# SignalGen_SingleChannel.net
KiCad netlist of a schematic drawn in Altium Designer
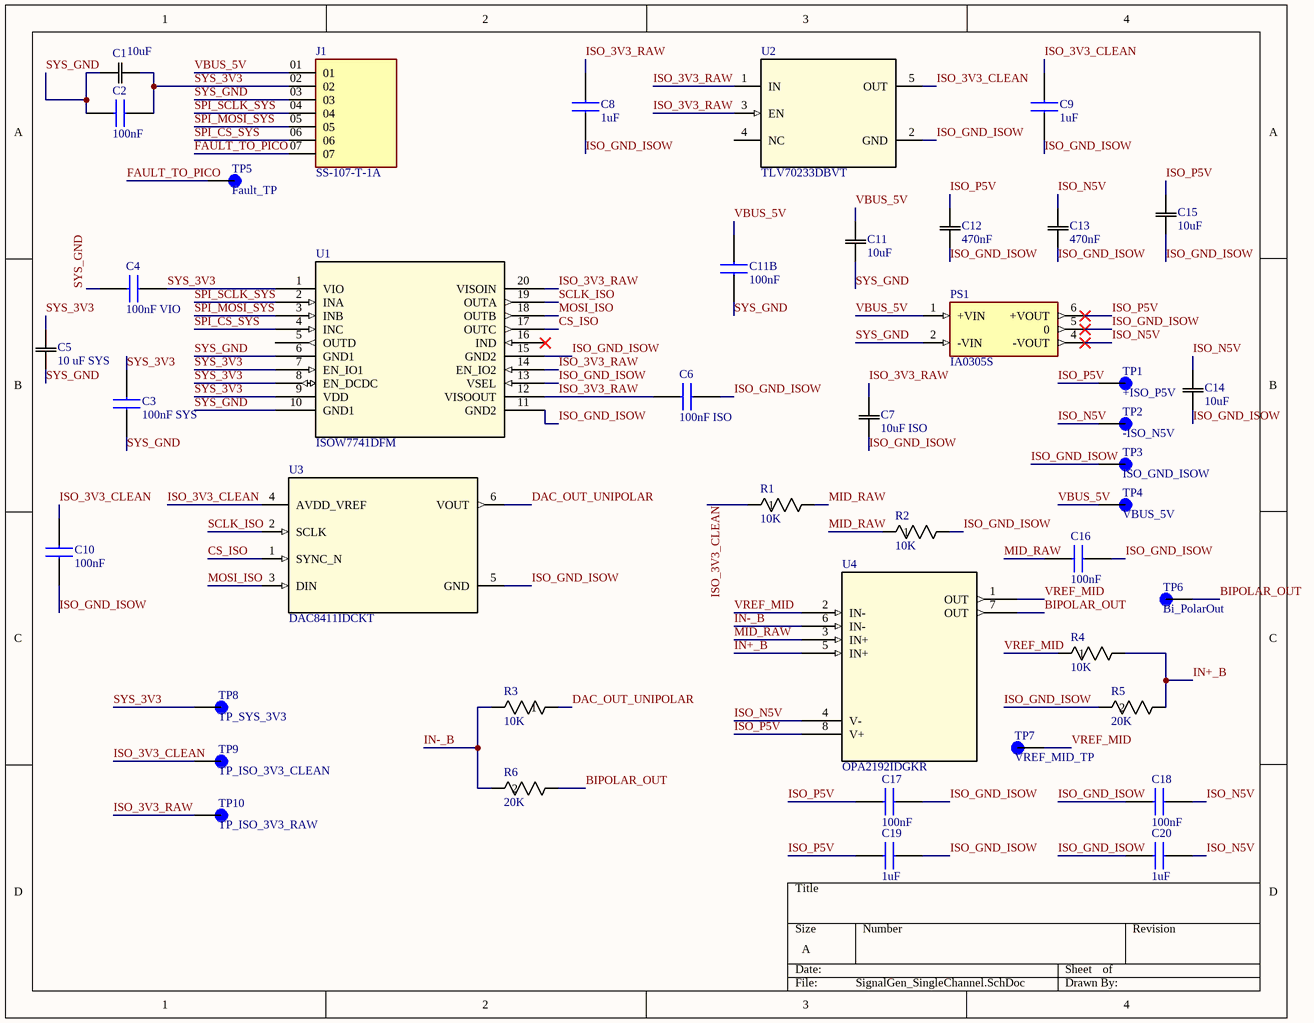
[diagram p0: SignalGen_SingleChannel.SchDoc]

(export (version "E")
  (design (tool "Eeschema 10.0.6"))
  (components
    (comp (ref "C1")
      (value "10uF")
      (footprint "G-21_MUR")
      (description "Description")
      (fields
        (field (name "MANUFACTURER_PART_NUMBER") "GRM21BR61E106KA73L")
        (field (name "COPYRIGHT") "Copyright (C) 2025 Ultra Librarian. All rights reserved.")
      )
      (libsource (lib "GRM21BR61E106KA73L") (part "GRM21BR61E106KA73L"))
    )
    (comp (ref "C2")
      (value "100nF")
      (footprint "CAPC1608X90N")
      (description "Cap Ceramic 0.1uF 25V X7R 10% Pad SMD 0603 125C T/R")
      (fields
        (field (name "MOUSER PART NUMBER") "603-CC603KRX7R8BB104")
        (field (name "MANUFACTURER_PART_NUMBER") "CC0603KRX7R8BB104")
      )
      (libsource (lib "CC0603KRX7R8BB104") (part "CC0603KRX7R8BB104"))
    )
    (comp (ref "C3")
      (value "100nF SYS")
      (footprint "CAPC1608X90N")
      (description "Cap Ceramic 0.1uF 25V X7R 10% Pad SMD 0603 125C T/R")
      (fields
        (field (name "MOUSER PART NUMBER") "603-CC603KRX7R8BB104")
        (field (name "MANUFACTURER_PART_NUMBER") "CC0603KRX7R8BB104")
      )
      (libsource (lib "CC0603KRX7R8BB104") (part "CC0603KRX7R8BB104"))
    )
    (comp (ref "C4")
      (value "100nF VIO")
      (footprint "CAPC1608X90N")
      (description "Cap Ceramic 0.1uF 25V X7R 10% Pad SMD 0603 125C T/R")
      (fields
        (field (name "MOUSER PART NUMBER") "603-CC603KRX7R8BB104")
        (field (name "MANUFACTURER_PART_NUMBER") "CC0603KRX7R8BB104")
      )
      (libsource (lib "CC0603KRX7R8BB104") (part "CC0603KRX7R8BB104"))
    )
    (comp (ref "C5")
      (value "10 uF SYS")
      (footprint "G-21_MUR")
      (description "Description")
      (fields
        (field (name "MANUFACTURER_PART_NUMBER") "GRM21BR61E106KA73L")
        (field (name "COPYRIGHT") "Copyright (C) 2025 Ultra Librarian. All rights reserved.")
      )
      (libsource (lib "GRM21BR61E106KA73L") (part "GRM21BR61E106KA73L"))
    )
    (comp (ref "C6")
      (value "100nF ISO")
      (footprint "CAPC1608X90N")
      (description "Cap Ceramic 0.1uF 25V X7R 10% Pad SMD 0603 125C T/R")
      (fields
        (field (name "MOUSER PART NUMBER") "603-CC603KRX7R8BB104")
        (field (name "MANUFACTURER_PART_NUMBER") "CC0603KRX7R8BB104")
      )
      (libsource (lib "CC0603KRX7R8BB104") (part "CC0603KRX7R8BB104"))
    )
    (comp (ref "C7")
      (value "10uF ISO")
      (footprint "G-21_MUR")
      (description "Description")
      (fields
        (field (name "MANUFACTURER_PART_NUMBER") "GRM21BR61E106KA73L")
        (field (name "COPYRIGHT") "Copyright (C) 2025 Ultra Librarian. All rights reserved.")
      )
      (libsource (lib "GRM21BR61E106KA73L") (part "GRM21BR61E106KA73L"))
    )
    (comp (ref "C8")
      (value "1uF")
      (footprint "INDC1608X90N")
      (description "Taiyo Yuden CAP, MLCC, 0603, 16V, X7R, 1 uF 10 %, T&R")
      (fields (field (name "MANUFACTURER_PART_NUMBER") "MBASE168SB7105KTNA18"))
      (libsource (lib "MBASE168SB7105KTNA18") (part "MBASE168SB7105KTNA18"))
    )
    (comp (ref "C9")
      (value "1uF")
      (footprint "INDC1608X90N")
      (description "Taiyo Yuden CAP, MLCC, 0603, 16V, X7R, 1 uF 10 %, T&R")
      (fields (field (name "MANUFACTURER_PART_NUMBER") "MBASE168SB7105KTNA18"))
      (libsource (lib "MBASE168SB7105KTNA18") (part "MBASE168SB7105KTNA18"))
    )
    (comp (ref "C10")
      (value "100nF")
      (footprint "CAPC1608X90N")
      (description "Cap Ceramic 0.1uF 25V X7R 10% Pad SMD 0603 125C T/R")
      (fields
        (field (name "MOUSER PART NUMBER") "603-CC603KRX7R8BB104")
        (field (name "MANUFACTURER_PART_NUMBER") "CC0603KRX7R8BB104")
      )
      (libsource (lib "CC0603KRX7R8BB104") (part "CC0603KRX7R8BB104"))
    )
    (comp (ref "C11")
      (value "10uF")
      (footprint "G-21_MUR")
      (description "Description")
      (fields
        (field (name "MANUFACTURER_PART_NUMBER") "GRM21BR61E106KA73L")
        (field (name "COPYRIGHT") "Copyright (C) 2025 Ultra Librarian. All rights reserved.")
      )
      (libsource (lib "GRM21BR61E106KA73L") (part "GRM21BR61E106KA73L"))
    )
    (comp (ref "C11B")
      (value "100nF")
      (footprint "CAPC1608X90N")
      (description "Cap Ceramic 0.1uF 25V X7R 10% Pad SMD 0603 125C T/R")
      (fields
        (field (name "MOUSER PART NUMBER") "603-CC603KRX7R8BB104")
        (field (name "MANUFACTURER_PART_NUMBER") "CC0603KRX7R8BB104")
      )
      (libsource (lib "CC0603KRX7R8BB104") (part "CC0603KRX7R8BB104"))
    )
    (comp (ref "C12")
      (value "470nF")
      (footprint "CAP_1608_TDK")
      (description "CAPACITOR; SMT (0603); CERAMIC CHIP; 0.47UF; 50V; TOL=10%; TG=-55 DEGC TO +125 DEGC; TC=X7R; AUTO")
      (fields
        (field (name "MANUFACTURER_PART_NUMBER") "C1608X7R1H474K080AC")
        (field (name "COPYRIGHT") "Copyright (C) 2026 Ultra Librarian. All rights reserved.")
      )
      (libsource (lib "C1608X7R1H474K080AC") (part "C1608X7R1H474K080AC"))
    )
    (comp (ref "C13")
      (value "470nF")
      (footprint "CAP_1608_TDK")
      (description "CAPACITOR; SMT (0603); CERAMIC CHIP; 0.47UF; 50V; TOL=10%; TG=-55 DEGC TO +125 DEGC; TC=X7R; AUTO")
      (fields
        (field (name "MANUFACTURER_PART_NUMBER") "C1608X7R1H474K080AC")
        (field (name "COPYRIGHT") "Copyright (C) 2026 Ultra Librarian. All rights reserved.")
      )
      (libsource (lib "C1608X7R1H474K080AC") (part "C1608X7R1H474K080AC"))
    )
    (comp (ref "C14")
      (value "10uF")
      (footprint "G-21_MUR")
      (description "Description")
      (fields
        (field (name "MANUFACTURER_PART_NUMBER") "GRM21BR61E106KA73L")
        (field (name "COPYRIGHT") "Copyright (C) 2025 Ultra Librarian. All rights reserved.")
      )
      (libsource (lib "GRM21BR61E106KA73L") (part "GRM21BR61E106KA73L"))
    )
    (comp (ref "C15")
      (value "10uF")
      (footprint "G-21_MUR")
      (description "Description")
      (fields
        (field (name "MANUFACTURER_PART_NUMBER") "GRM21BR61E106KA73L")
        (field (name "COPYRIGHT") "Copyright (C) 2025 Ultra Librarian. All rights reserved.")
      )
      (libsource (lib "GRM21BR61E106KA73L") (part "GRM21BR61E106KA73L"))
    )
    (comp (ref "C16")
      (value "100nF")
      (footprint "CAPC1608X90N")
      (description "Cap Ceramic 0.1uF 25V X7R 10% Pad SMD 0603 125C T/R")
      (fields
        (field (name "MOUSER PART NUMBER") "603-CC603KRX7R8BB104")
        (field (name "MANUFACTURER_PART_NUMBER") "CC0603KRX7R8BB104")
      )
      (libsource (lib "CC0603KRX7R8BB104") (part "CC0603KRX7R8BB104"))
    )
    (comp (ref "C17")
      (value "100nF")
      (footprint "CAPC1608X90N")
      (description "Cap Ceramic 0.1uF 25V X7R 10% Pad SMD 0603 125C T/R")
      (fields
        (field (name "MOUSER PART NUMBER") "603-CC603KRX7R8BB104")
        (field (name "MANUFACTURER_PART_NUMBER") "CC0603KRX7R8BB104")
      )
      (libsource (lib "CC0603KRX7R8BB104") (part "CC0603KRX7R8BB104"))
    )
    (comp (ref "C18")
      (value "100nF")
      (footprint "CAPC1608X90N")
      (description "Cap Ceramic 0.1uF 25V X7R 10% Pad SMD 0603 125C T/R")
      (fields
        (field (name "MOUSER PART NUMBER") "603-CC603KRX7R8BB104")
        (field (name "MANUFACTURER_PART_NUMBER") "CC0603KRX7R8BB104")
      )
      (libsource (lib "CC0603KRX7R8BB104") (part "CC0603KRX7R8BB104"))
    )
    (comp (ref "C19")
      (value "1uF")
      (footprint "INDC1608X90N")
      (description "Taiyo Yuden CAP, MLCC, 0603, 16V, X7R, 1 uF 10 %, T&R")
      (fields (field (name "MANUFACTURER_PART_NUMBER") "MBASE168SB7105KTNA18"))
      (libsource (lib "MBASE168SB7105KTNA18") (part "MBASE168SB7105KTNA18"))
    )
    (comp (ref "C20")
      (value "1uF")
      (footprint "INDC1608X90N")
      (description "Taiyo Yuden CAP, MLCC, 0603, 16V, X7R, 1 uF 10 %, T&R")
      (fields (field (name "MANUFACTURER_PART_NUMBER") "MBASE168SB7105KTNA18"))
      (libsource (lib "MBASE168SB7105KTNA18") (part "MBASE168SB7105KTNA18"))
    )
    (comp (ref "J1")
      (value "SS-107-T-1A")
      (footprint "SAMTEC_SS-107-T-1A")
      (libsource (lib "SS-107-T-1A") (part "SS-107-T-1A"))
    )
    (comp (ref "PS1")
      (value "IA0305S")
      (footprint "XP_IA0305S")
      (description "DC DC CONVERTER +/-5V 1W")
      (libsource (lib "IA0305S") (part "IA0305S"))
    )
    (comp (ref "R1")
      (value "10K")
      (footprint "RC0603N_YAG")
      (description "RES SMD 10kO 1% 1/10W 0603")
      (fields
        (field (name "MANUFACTURER_PART_NUMBER") "RC0603FR-0710KL")
        (field (name "COPYRIGHT") "Copyright (C) 2025 Ultra Librarian. All rights reserved.")
      )
      (libsource (lib "RC0603FR-0710KL") (part "RC0603FR-0710KL"))
    )
    (comp (ref "R2")
      (value "10K")
      (footprint "RC0603N_YAG")
      (description "RES SMD 10kO 1% 1/10W 0603")
      (fields
        (field (name "MANUFACTURER_PART_NUMBER") "RC0603FR-0710KL")
        (field (name "COPYRIGHT") "Copyright (C) 2025 Ultra Librarian. All rights reserved.")
      )
      (libsource (lib "RC0603FR-0710KL") (part "RC0603FR-0710KL"))
    )
    (comp (ref "R3")
      (value "10K")
      (footprint "RC0603N_YAG")
      (description "RES SMD 10kO 1% 1/10W 0603")
      (fields
        (field (name "MANUFACTURER_PART_NUMBER") "RC0603FR-0710KL")
        (field (name "COPYRIGHT") "Copyright (C) 2025 Ultra Librarian. All rights reserved.")
      )
      (libsource (lib "RC0603FR-0710KL") (part "RC0603FR-0710KL"))
    )
    (comp (ref "R4")
      (value "10K")
      (footprint "RC0603N_YAG")
      (description "RES SMD 10kO 1% 1/10W 0603")
      (fields
        (field (name "MANUFACTURER_PART_NUMBER") "RC0603FR-0710KL")
        (field (name "COPYRIGHT") "Copyright (C) 2025 Ultra Librarian. All rights reserved.")
      )
      (libsource (lib "RC0603FR-0710KL") (part "RC0603FR-0710KL"))
    )
    (comp (ref "R5")
      (value "20K")
      (footprint "RC0603N_YAG")
      (description "Description")
      (fields
        (field (name "MANUFACTURER_PART_NUMBER") "RC0603FR-0720KL")
        (field (name "COPYRIGHT") "Copyright (C) 2025 Ultra Librarian. All rights reserved.")
      )
      (libsource (lib "RC0603FR-0720KL") (part "RC0603FR-0720KL"))
    )
    (comp (ref "R6")
      (value "20K")
      (footprint "RC0603N_YAG")
      (description "Description")
      (fields
        (field (name "MANUFACTURER_PART_NUMBER") "RC0603FR-0720KL")
        (field (name "COPYRIGHT") "Copyright (C) 2025 Ultra Librarian. All rights reserved.")
      )
      (libsource (lib "RC0603FR-0720KL") (part "RC0603FR-0720KL"))
    )
    (comp (ref "TP1")
      (value "+ISO_P5V")
      (footprint "KEYSTONE_5016")
      (description "Test Point Compact SMT Phos Bronze/Silver 1000pc Tape & Reel ¦ Keystone Electronics 5016")
      (fields (field (name "MF") "Keystone Electronics") (field (name "MP") "5016"))
      (libsource (lib "5016") (part "5016"))
    )
    (comp (ref "TP2")
      (value "-ISO_N5V")
      (footprint "KEYSTONE_5016")
      (description "Test Point Compact SMT Phos Bronze/Silver 1000pc Tape & Reel ¦ Keystone Electronics 5016")
      (fields (field (name "MF") "Keystone Electronics") (field (name "MP") "5016"))
      (libsource (lib "5016") (part "5016"))
    )
    (comp (ref "TP3")
      (value "ISO_GND_ISOW")
      (footprint "KEYSTONE_5016")
      (description "Test Point Compact SMT Phos Bronze/Silver 1000pc Tape & Reel ¦ Keystone Electronics 5016")
      (fields (field (name "MF") "Keystone Electronics") (field (name "MP") "5016"))
      (libsource (lib "5016") (part "5016"))
    )
    (comp (ref "TP4")
      (value "VBUS_5V")
      (footprint "KEYSTONE_5016")
      (description "Test Point Compact SMT Phos Bronze/Silver 1000pc Tape & Reel ¦ Keystone Electronics 5016")
      (fields (field (name "MF") "Keystone Electronics") (field (name "MP") "5016"))
      (libsource (lib "5016") (part "5016"))
    )
    (comp (ref "TP5")
      (value "Fault_TP")
      (footprint "KEYSTONE_5016")
      (description "Test Point Compact SMT Phos Bronze/Silver 1000pc Tape & Reel ¦ Keystone Electronics 5016")
      (fields (field (name "MF") "Keystone Electronics") (field (name "MP") "5016"))
      (libsource (lib "5016") (part "5016"))
    )
    (comp (ref "TP6")
      (value "Bi_PolarOut")
      (footprint "KEYSTONE_5016")
      (description "Test Point Compact SMT Phos Bronze/Silver 1000pc Tape & Reel ¦ Keystone Electronics 5016")
      (fields (field (name "MF") "Keystone Electronics") (field (name "MP") "5016"))
      (libsource (lib "5016") (part "5016"))
    )
    (comp (ref "TP7")
      (value "VREF_MID_TP")
      (footprint "KEYSTONE_5016")
      (description "Test Point Compact SMT Phos Bronze/Silver 1000pc Tape & Reel ¦ Keystone Electronics 5016")
      (fields (field (name "MF") "Keystone Electronics") (field (name "MP") "5016"))
      (libsource (lib "5016") (part "5016"))
    )
    (comp (ref "TP8")
      (value "TP_SYS_3V3")
      (footprint "KEYSTONE_5016")
      (description "Test Point Compact SMT Phos Bronze/Silver 1000pc Tape & Reel ¦ Keystone Electronics 5016")
      (fields (field (name "MF") "Keystone Electronics") (field (name "MP") "5016"))
      (libsource (lib "5016") (part "5016"))
    )
    (comp (ref "TP9")
      (value "TP_ISO_3V3_CLEAN")
      (footprint "KEYSTONE_5016")
      (description "Test Point Compact SMT Phos Bronze/Silver 1000pc Tape & Reel ¦ Keystone Electronics 5016")
      (fields (field (name "MF") "Keystone Electronics") (field (name "MP") "5016"))
      (libsource (lib "5016") (part "5016"))
    )
    (comp (ref "TP10")
      (value "TP_ISO_3V3_RAW")
      (footprint "KEYSTONE_5016")
      (description "Test Point Compact SMT Phos Bronze/Silver 1000pc Tape & Reel ¦ Keystone Electronics 5016")
      (fields (field (name "MF") "Keystone Electronics") (field (name "MP") "5016"))
      (libsource (lib "5016") (part "5016"))
    )
    (comp (ref "U1")
      (value "ISOW7741DFM")
      (footprint "SOIC20_DFM_TEX")
      (fields (field (name "COPYRIGHT") "Copyright (C) 2026 Ultra Librarian. All rights reserved."))
      (libsource (lib "ISOW7741DFM") (part "ISOW7741DFM"))
    )
    (comp (ref "U2")
      (value "TLV70233DBVT")
      (footprint "DBV0005A_N")
      (description "300-mA, high-PSRR, low-IQ, low-dropout voltage regulator with enable 5-SOT-23 -40 to 125")
      (fields
        (field (name "PARTNUMBER") "TLV70212DBVR")
        (field (name "ALTERNATE_PARTNUMBER") "TLV70212DBVT")
        (field (name "COPYRIGHT") "Copyright (C) 2026 Ultra Librarian. All rights reserved.")
      )
      (libsource (lib "TLV70233DBVT") (part "TLV70233DBVT"))
    )
    (comp (ref "U3")
      (value "DAC8411IDCKT")
      (footprint "DCK0006A_N")
      (description "16bit, Single Channel, 80uA, 2.0V-5.5V DAC in SC70 Package 6-SC70 -40 to 125")
      (fields
        (field (name "PARTNUMBER") "DAC8411IDCKR")
        (field (name "MANUFACTURER") "Texas Instruments")
        (field (name "COPYRIGHT") "Copyright (C) 2025 Ultra Librarian. All rights reserved.")
      )
      (libsource (lib "DAC8411IDCKT") (part "DAC8411IDCKT"))
    )
    (comp (ref "U4")
      (value "OPA2192IDGKR")
      (footprint "DGK0008A_N_TEX")
      (fields (field (name "COPYRIGHT") "Copyright (C) 2025 Ultra Librarian. All rights reserved."))
      (libsource (lib "OPA2192IDGKR") (part "OPA2192IDGKR"))
    )
  )
  (nets
    (net (code "1") (name "/BIPOLAR_OUT") (class "Default")
      (node (ref "R6") (pin "1") (pinfunction "1_1") (pintype "passive"))
      (node (ref "TP6") (pin "TP") (pinfunction "TP_TP") (pintype "passive"))
      (node (ref "U4") (pin "7") (pinfunction "OUT_7") (pintype "output"))
    )
    (net (code "2") (name "/CS_ISO") (class "Default")
      (node (ref "U1") (pin "17") (pinfunction "OUTC_17") (pintype "output"))
      (node (ref "U3") (pin "1") (pinfunction "SYNC_N_1") (pintype "input"))
    )
    (net (code "3") (name "/DAC_OUT_UNIPOLAR") (class "Default")
      (node (ref "R3") (pin "1") (pinfunction "1_1") (pintype "passive"))
      (node (ref "U3") (pin "6") (pinfunction "VOUT_6") (pintype "output"))
    )
    (net (code "4") (name "/FAULT_TO_PICO") (class "Default")
      (node (ref "J1") (pin "07") (pinfunction "07_07") (pintype "passive"))
      (node (ref "TP5") (pin "TP") (pinfunction "TP_TP") (pintype "passive"))
    )
    (net (code "5") (name "/IN+_B") (class "Default")
      (node (ref "R4") (pin "2") (pinfunction "2_2") (pintype "passive"))
      (node (ref "R5") (pin "1") (pinfunction "1_1") (pintype "passive"))
      (node (ref "U4") (pin "5") (pinfunction "IN+_5") (pintype "input"))
    )
    (net (code "6") (name "/IN-_B") (class "Default")
      (node (ref "R3") (pin "2") (pinfunction "2_2") (pintype "passive"))
      (node (ref "R6") (pin "2") (pinfunction "2_2") (pintype "passive"))
      (node (ref "U4") (pin "6") (pinfunction "IN-_6") (pintype "input"))
    )
    (net (code "7") (name "/ISO_3V3_CLEAN") (class "Default")
      (node (ref "C10") (pin "2") (pinfunction "2_2") (pintype "passive"))
      (node (ref "C9") (pin "2") (pinfunction "2_2") (pintype "passive"))
      (node (ref "R1") (pin "1") (pinfunction "1_1") (pintype "passive"))
      (node (ref "TP9") (pin "TP") (pinfunction "TP_TP") (pintype "passive"))
      (node (ref "U2") (pin "5") (pinfunction "OUT_5") (pintype "power_in"))
      (node (ref "U3") (pin "4") (pinfunction "AVDD_VREF_4") (pintype "power_in"))
    )
    (net (code "8") (name "/ISO_3V3_RAW") (class "Default")
      (node (ref "C6") (pin "2") (pinfunction "2_2") (pintype "passive"))
      (node (ref "C7") (pin "2") (pinfunction "2_2") (pintype "passive"))
      (node (ref "C8") (pin "2") (pinfunction "2_2") (pintype "passive"))
      (node (ref "TP10") (pin "TP") (pinfunction "TP_TP") (pintype "passive"))
      (node (ref "U1") (pin "12") (pinfunction "VISOOUT_12") (pintype "power_in"))
      (node (ref "U1") (pin "14") (pinfunction "EN_IO2_14") (pintype "input"))
      (node (ref "U1") (pin "20") (pinfunction "VISOIN_20") (pintype "power_in"))
      (node (ref "U2") (pin "1") (pinfunction "IN_1") (pintype "power_in"))
      (node (ref "U2") (pin "3") (pinfunction "EN_3") (pintype "input"))
    )
    (net (code "9") (name "/ISO_GND_ISOW") (class "Default")
      (node (ref "C10") (pin "1") (pinfunction "1_1") (pintype "passive"))
      (node (ref "C12") (pin "1") (pinfunction "1_1") (pintype "passive"))
      (node (ref "C13") (pin "1") (pinfunction "1_1") (pintype "passive"))
      (node (ref "C14") (pin "1") (pinfunction "1_1") (pintype "passive"))
      (node (ref "C15") (pin "1") (pinfunction "1_1") (pintype "passive"))
      (node (ref "C16") (pin "2") (pinfunction "2_2") (pintype "passive"))
      (node (ref "C17") (pin "2") (pinfunction "2_2") (pintype "passive"))
      (node (ref "C18") (pin "1") (pinfunction "1_1") (pintype "passive"))
      (node (ref "C19") (pin "2") (pinfunction "2_2") (pintype "passive"))
      (node (ref "C20") (pin "1") (pinfunction "1_1") (pintype "passive"))
      (node (ref "C6") (pin "1") (pinfunction "1_1") (pintype "passive"))
      (node (ref "C7") (pin "1") (pinfunction "1_1") (pintype "passive"))
      (node (ref "C8") (pin "1") (pinfunction "1_1") (pintype "passive"))
      (node (ref "C9") (pin "1") (pinfunction "1_1") (pintype "passive"))
      (node (ref "PS1") (pin "5") (pinfunction "0_5") (pintype "output"))
      (node (ref "R2") (pin "2") (pinfunction "2_2") (pintype "passive"))
      (node (ref "R5") (pin "2") (pinfunction "2_2") (pintype "passive"))
      (node (ref "TP3") (pin "TP") (pinfunction "TP_TP") (pintype "passive"))
      (node (ref "U1") (pin "11") (pinfunction "GND2_11") (pintype "power_in"))
      (node (ref "U1") (pin "13") (pinfunction "VSEL_13") (pintype "input"))
      (node (ref "U1") (pin "15") (pinfunction "GND2_15") (pintype "power_in"))
      (node (ref "U2") (pin "2") (pinfunction "GND_2") (pintype "power_in"))
      (node (ref "U3") (pin "5") (pinfunction "GND_5") (pintype "power_in"))
    )
    (net (code "10") (name "/ISO_N5V") (class "Default")
      (node (ref "C13") (pin "2") (pinfunction "2_2") (pintype "passive"))
      (node (ref "C14") (pin "2") (pinfunction "2_2") (pintype "passive"))
      (node (ref "C18") (pin "2") (pinfunction "2_2") (pintype "passive"))
      (node (ref "C20") (pin "2") (pinfunction "2_2") (pintype "passive"))
      (node (ref "PS1") (pin "4") (pinfunction "-VOUT_4") (pintype "output"))
      (node (ref "TP2") (pin "TP") (pinfunction "TP_TP") (pintype "passive"))
      (node (ref "U4") (pin "4") (pinfunction "V-_4") (pintype "power_in"))
    )
    (net (code "11") (name "/ISO_P5V") (class "Default")
      (node (ref "C12") (pin "2") (pinfunction "2_2") (pintype "passive"))
      (node (ref "C15") (pin "2") (pinfunction "2_2") (pintype "passive"))
      (node (ref "C17") (pin "1") (pinfunction "1_1") (pintype "passive"))
      (node (ref "C19") (pin "1") (pinfunction "1_1") (pintype "passive"))
      (node (ref "PS1") (pin "6") (pinfunction "+VOUT_6") (pintype "output"))
      (node (ref "TP1") (pin "TP") (pinfunction "TP_TP") (pintype "passive"))
      (node (ref "U4") (pin "8") (pinfunction "V+_8") (pintype "power_in"))
    )
    (net (code "12") (name "/MID_RAW") (class "Default")
      (node (ref "C16") (pin "1") (pinfunction "1_1") (pintype "passive"))
      (node (ref "R1") (pin "2") (pinfunction "2_2") (pintype "passive"))
      (node (ref "R2") (pin "1") (pinfunction "1_1") (pintype "passive"))
      (node (ref "U4") (pin "3") (pinfunction "IN+_3") (pintype "input"))
    )
    (net (code "13") (name "/MOSI_ISO") (class "Default")
      (node (ref "U1") (pin "18") (pinfunction "OUTB_18") (pintype "output"))
      (node (ref "U3") (pin "3") (pinfunction "DIN_3") (pintype "input"))
    )
    (net (code "14") (name "/SCLK_ISO") (class "Default")
      (node (ref "U1") (pin "19") (pinfunction "OUTA_19") (pintype "output"))
      (node (ref "U3") (pin "2") (pinfunction "SCLK_2") (pintype "input"))
    )
    (net (code "15") (name "/SPI_CS_SYS") (class "Default")
      (node (ref "J1") (pin "06") (pinfunction "06_06") (pintype "passive"))
      (node (ref "U1") (pin "4") (pinfunction "INC_4") (pintype "input"))
    )
    (net (code "16") (name "/SPI_MOSI_SYS") (class "Default")
      (node (ref "J1") (pin "05") (pinfunction "05_05") (pintype "passive"))
      (node (ref "U1") (pin "3") (pinfunction "INB_3") (pintype "input"))
    )
    (net (code "17") (name "/SPI_SCLK_SYS") (class "Default")
      (node (ref "J1") (pin "04") (pinfunction "04_04") (pintype "passive"))
      (node (ref "U1") (pin "2") (pinfunction "INA_2") (pintype "input"))
    )
    (net (code "18") (name "/SYS_3V3") (class "Default")
      (node (ref "C1") (pin "1") (pinfunction "1_1") (pintype "passive"))
      (node (ref "C2") (pin "1") (pinfunction "1_1") (pintype "passive"))
      (node (ref "C3") (pin "2") (pinfunction "2_2") (pintype "passive"))
      (node (ref "C4") (pin "1") (pinfunction "1_1") (pintype "passive"))
      (node (ref "C5") (pin "2") (pinfunction "2_2") (pintype "passive"))
      (node (ref "J1") (pin "02") (pinfunction "02_02") (pintype "passive"))
      (node (ref "TP8") (pin "TP") (pinfunction "TP_TP") (pintype "passive"))
      (node (ref "U1") (pin "1") (pinfunction "VIO_1") (pintype "power_in"))
      (node (ref "U1") (pin "7") (pinfunction "EN_IO1_7") (pintype "input"))
      (node (ref "U1") (pin "8") (pinfunction "EN_DCDC_8") (pintype "bidirectional"))
      (node (ref "U1") (pin "9") (pinfunction "VDD_9") (pintype "power_in"))
    )
    (net (code "19") (name "/SYS_GND") (class "Default")
      (node (ref "C1") (pin "2") (pinfunction "2_2") (pintype "passive"))
      (node (ref "C11") (pin "1") (pinfunction "1_1") (pintype "passive"))
      (node (ref "C11B") (pin "1") (pinfunction "1_1") (pintype "passive"))
      (node (ref "C2") (pin "2") (pinfunction "2_2") (pintype "passive"))
      (node (ref "C3") (pin "1") (pinfunction "1_1") (pintype "passive"))
      (node (ref "C4") (pin "2") (pinfunction "2_2") (pintype "passive"))
      (node (ref "C5") (pin "1") (pinfunction "1_1") (pintype "passive"))
      (node (ref "J1") (pin "03") (pinfunction "03_03") (pintype "passive"))
      (node (ref "PS1") (pin "2") (pinfunction "-VIN_2") (pintype "input"))
      (node (ref "U1") (pin "10") (pinfunction "GND1_10") (pintype "power_in"))
      (node (ref "U1") (pin "6") (pinfunction "GND1_6") (pintype "power_in"))
    )
    (net (code "20") (name "/VBUS_5V") (class "Default")
      (node (ref "C11") (pin "2") (pinfunction "2_2") (pintype "passive"))
      (node (ref "C11B") (pin "2") (pinfunction "2_2") (pintype "passive"))
      (node (ref "J1") (pin "01") (pinfunction "01_01") (pintype "passive"))
      (node (ref "PS1") (pin "1") (pinfunction "+VIN_1") (pintype "input"))
      (node (ref "TP4") (pin "TP") (pinfunction "TP_TP") (pintype "passive"))
    )
    (net (code "21") (name "/VREF_MID") (class "Default")
      (node (ref "R4") (pin "1") (pinfunction "1_1") (pintype "passive"))
      (node (ref "TP7") (pin "TP") (pinfunction "TP_TP") (pintype "passive"))
      (node (ref "U4") (pin "1") (pinfunction "OUT_1") (pintype "output"))
      (node (ref "U4") (pin "2") (pinfunction "IN-_2") (pintype "input"))
    )
    (net (code "22") (name "unconnected-(U1-IND-Pad16)") (class "Default")
      (node (ref "U1") (pin "16") (pinfunction "IND_16") (pintype "input+no_connect"))
    )
    (net (code "23") (name "unconnected-(U1-OUTD-Pad5)") (class "Default")
      (node (ref "U1") (pin "5") (pinfunction "OUTD_5") (pintype "output"))
    )
    (net (code "24") (name "unconnected-(U2-NC-Pad4)") (class "Default")
      (node (ref "U2") (pin "4") (pinfunction "NC_4") (pintype "passive"))
    )
  )
)
